# LDO-Schematic.net
KiCad netlist of a schematic drawn in Altium Designer
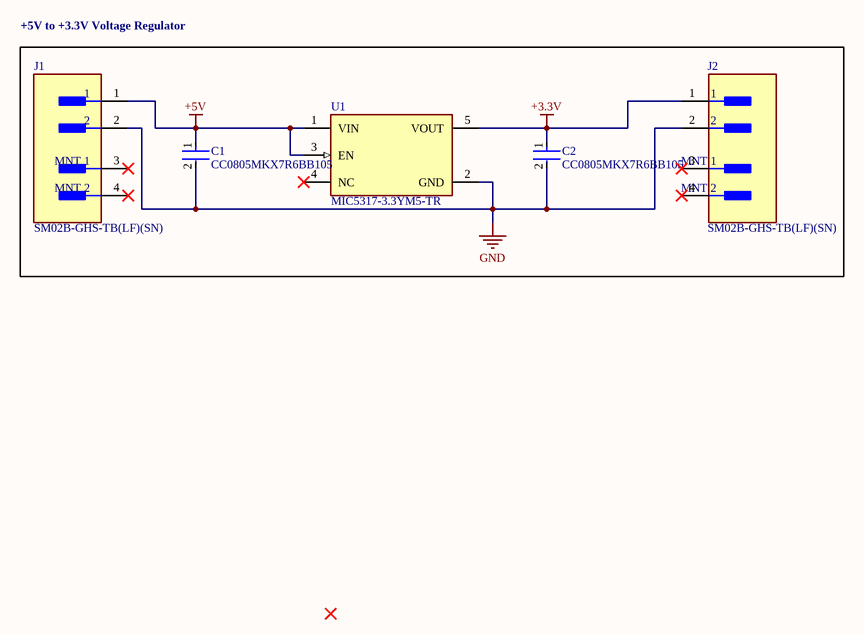
[diagram p0: LDO-Schematic.SchDoc]

(export (version "E")
  (design (tool "Eeschema 10.0.6"))
  (components
    (comp (ref "C1")
      (value "CC0805MKX7R6BB105")
      (footprint "FP-CC0805-0_85-MFG")
      (description "CAP CER 1UF 10V X7R 0805")
      (fields
        (field (name "OCTOPART") "https://octopart.com/cc0805mkx7r6bb105-yageo-71334590")
        (field (name "TOLERANCE") "0.2")
      )
      (libsource (lib "Altium Content Vault") (part "11868f565c42a9108669ba33697ecf6"))
    )
    (comp (ref "C2")
      (value "CC0805MKX7R6BB105")
      (footprint "FP-CC0805-0_85-MFG")
      (description "CAP CER 1UF 10V X7R 0805")
      (fields
        (field (name "OCTOPART") "https://octopart.com/cc0805mkx7r6bb105-yageo-71334590")
        (field (name "TOLERANCE") "0.2")
      )
      (libsource (lib "Altium Content Vault") (part "11868f565c42a9108669ba33697ecf6"))
    )
    (comp (ref "J1")
      (value "SM02B-GHS-TB(LF)(SN)")
      (footprint "FP-SM02B-GHS-TB_LF_SN-MFG")
      (description "CONN HEADER SMD R/A 2POS 1.25MM")
      (libsource (lib "Altium Content Vault") (part "56ec3178a87b3978bdc1b3682cd516a"))
    )
    (comp (ref "J2")
      (value "SM02B-GHS-TB(LF)(SN)")
      (footprint "FP-SM02B-GHS-TB_LF_SN-MFG")
      (description "CONN HEADER SMD R/A 2POS 1.25MM")
      (libsource (lib "") (part "56ec3178a87b3978bdc1b3682cd516a_1"))
    )
    (comp (ref "U1")
      (value "MIC5317-3.3YM5-TR")
      (footprint "FP-SOT23-5LD-PL-1-MFG")
      (description "IC REG LINEAR 3.3V 150MA SOT23-5")
      (libsource (lib "Altium Content Vault") (part "0a093dae7315cdc977fd108dde87457"))
    )
  )
  (nets
    (net (code "1") (name "+3.3V") (class "Default")
      (node (ref "C2") (pin "1") (pinfunction "1_1") (pintype "passive"))
      (node (ref "J2") (pin "1") (pinfunction "1_1") (pintype "passive"))
      (node (ref "U1") (pin "5") (pinfunction "VOUT_5") (pintype "power_in"))
    )
    (net (code "2") (name "+5V") (class "Default")
      (node (ref "C1") (pin "1") (pinfunction "1_1") (pintype "passive"))
      (node (ref "J1") (pin "1") (pinfunction "1_1") (pintype "passive"))
      (node (ref "U1") (pin "1") (pinfunction "VIN_1") (pintype "power_in"))
      (node (ref "U1") (pin "3") (pinfunction "EN_3") (pintype "input"))
    )
    (net (code "3") (name "GND") (class "Default")
      (node (ref "C1") (pin "2") (pinfunction "2_2") (pintype "passive"))
      (node (ref "C2") (pin "2") (pinfunction "2_2") (pintype "passive"))
      (node (ref "J1") (pin "2") (pinfunction "2_2") (pintype "passive"))
      (node (ref "J2") (pin "2") (pinfunction "2_2") (pintype "passive"))
      (node (ref "U1") (pin "2") (pinfunction "GND_2") (pintype "power_in"))
    )
    (net (code "4") (name "unconnected-(J1-MNT_1-Pad3)") (class "Default")
      (node (ref "J1") (pin "3") (pinfunction "MNT_1_3") (pintype "passive+no_connect"))
    )
    (net (code "5") (name "unconnected-(J1-MNT_2-Pad4)") (class "Default")
      (node (ref "J1") (pin "4") (pinfunction "MNT_2_4") (pintype "passive+no_connect"))
    )
    (net (code "6") (name "unconnected-(J2-MNT_1-Pad3)") (class "Default")
      (node (ref "J2") (pin "3") (pinfunction "MNT_1_3") (pintype "passive+no_connect"))
    )
    (net (code "7") (name "unconnected-(J2-MNT_2-Pad4)") (class "Default")
      (node (ref "J2") (pin "4") (pinfunction "MNT_2_4") (pintype "passive+no_connect"))
    )
    (net (code "8") (name "unconnected-(U1-NC-Pad4)") (class "Default")
      (node (ref "U1") (pin "4") (pinfunction "NC_4") (pintype "passive+no_connect"))
    )
  )
)
